# 5_-_Status_Lights.net
KiCad netlist of a schematic drawn in Altium Designer
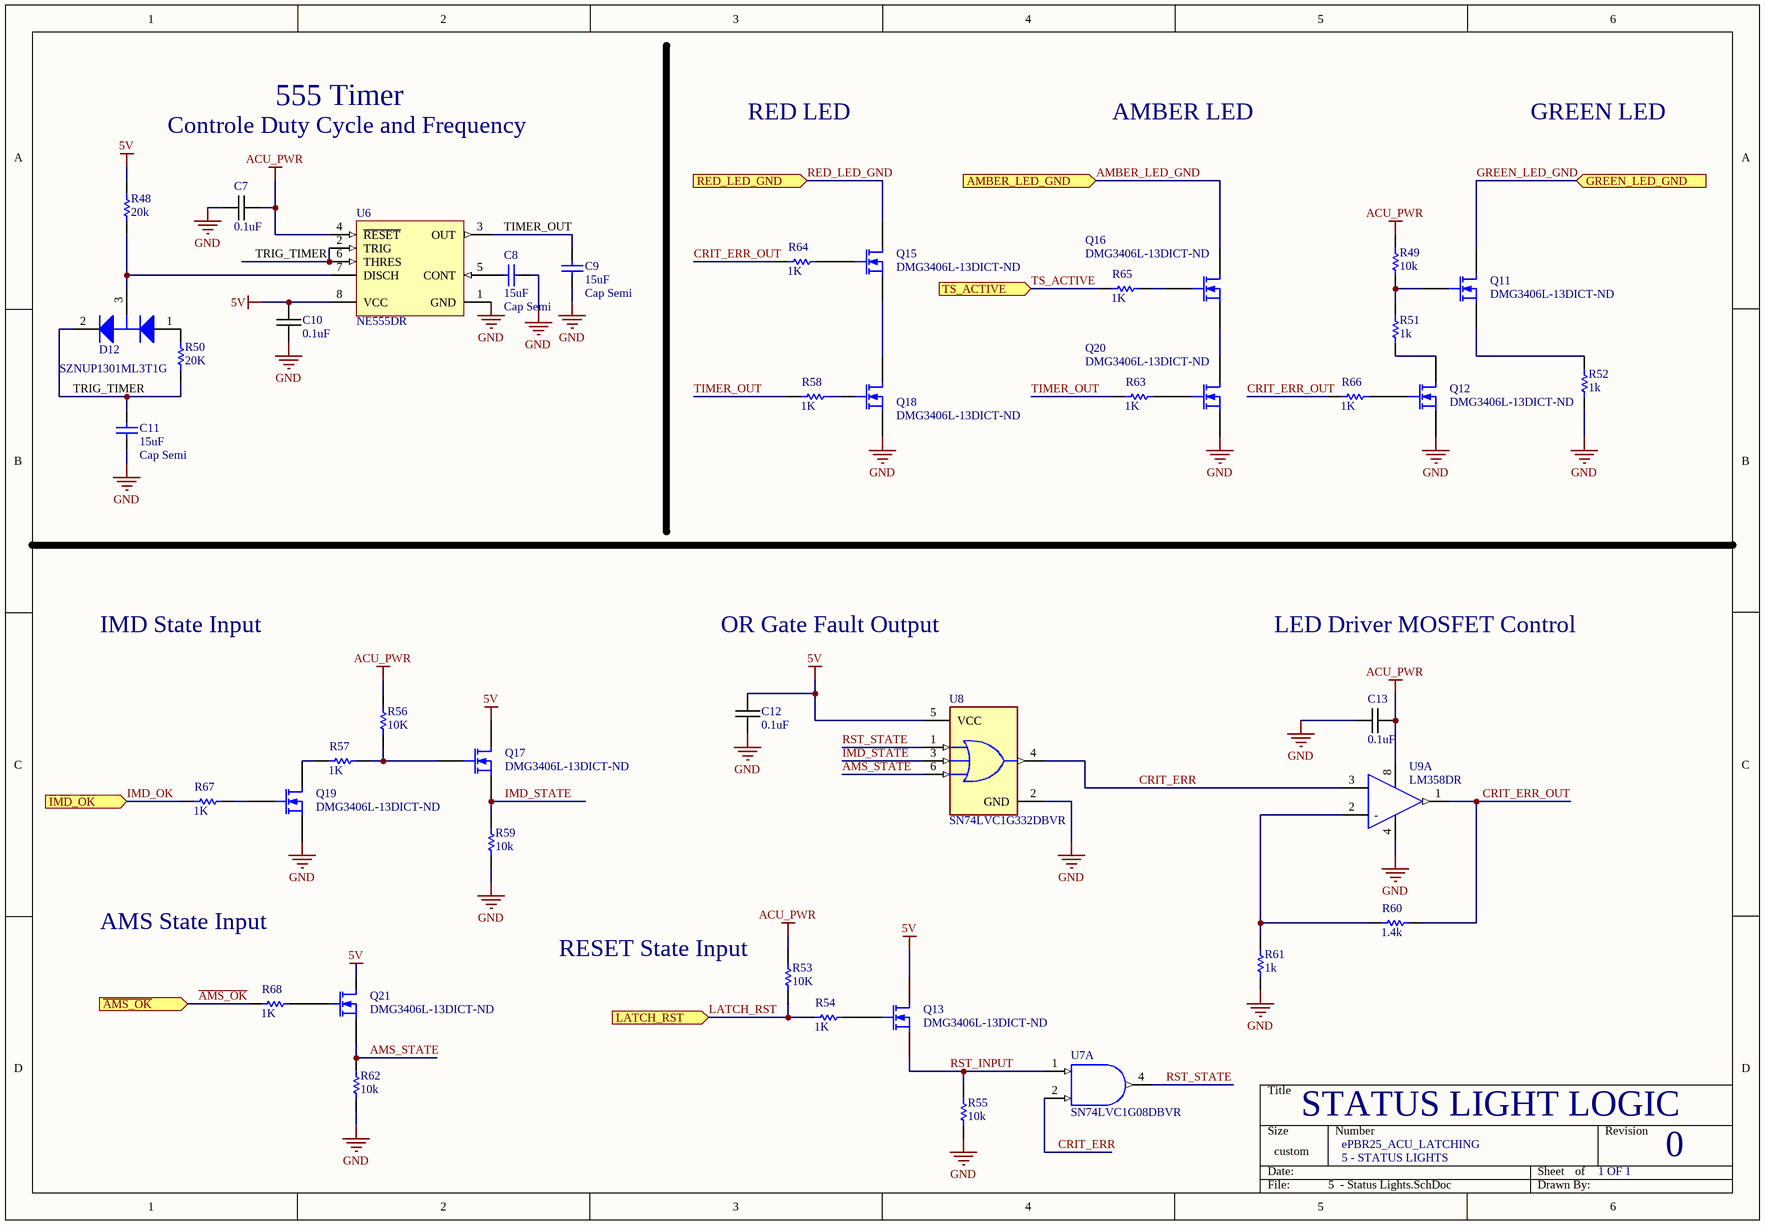
[diagram p0: 5  - Status Lights.SchDoc]

(export (version "E")
  (design (tool "Eeschema 10.0.6"))
  (components
    (comp (ref "C7")
      (value "0.1uF")
      (footprint "1608[0603]")
      (description "CAP CER 0.1UF 50V X7R 0603")
      (fields
        (field (name "MANUFACTURER") "Kemet")
        (field (name "MANUFACTURER PART NUMBER") "C0603C104K5RACAUTO")
      )
      (libsource (lib "vh_altium_library") (part "0805C-100nF-25V-X7R-MUR"))
    )
    (comp (ref "C8")
      (value "Cap Semi")
      (footprint "1608[0603]")
      (description "Capacitor (Semiconductor SIM Model)")
      (fields (field (name "ALTIUM_VALUE") "15uF") (field (name "PUBLISHER") "Altium Limited"))
      (libsource (lib "Miscellaneous Devices") (part "Cap Semi"))
    )
    (comp (ref "C9")
      (value "Cap Semi")
      (footprint "1608[0603]")
      (description "Capacitor (Semiconductor SIM Model)")
      (fields (field (name "ALTIUM_VALUE") "15uF") (field (name "PUBLISHER") "Altium Limited"))
      (libsource (lib "Miscellaneous Devices") (part "Cap Semi"))
    )
    (comp (ref "C10")
      (value "0.1uF")
      (footprint "1608[0603]")
      (description "CAP CER 0.1UF 50V X7R 0603")
      (fields
        (field (name "MANUFACTURER") "Kemet")
        (field (name "MANUFACTURER PART NUMBER") "C0603C104K5RACAUTO")
      )
      (libsource (lib "vh_altium_library") (part "0805C-100nF-25V-X7R-MUR"))
    )
    (comp (ref "C11")
      (value "Cap Semi")
      (footprint "1608[0603]")
      (description "Capacitor (Semiconductor SIM Model)")
      (fields (field (name "ALTIUM_VALUE") "15uF") (field (name "PUBLISHER") "Altium Limited"))
      (libsource (lib "Miscellaneous Devices") (part "Cap Semi"))
    )
    (comp (ref "C12")
      (value "0.1uF")
      (footprint "1608[0603]")
      (description "CAP CER 0.1UF 50V X7R 0603")
      (fields
        (field (name "MANUFACTURER") "Kemet")
        (field (name "MANUFACTURER PART NUMBER") "C0603C104K5RACAUTO")
      )
      (libsource (lib "vh_altium_library") (part "0805C-100nF-25V-X7R-MUR"))
    )
    (comp (ref "C13")
      (value "0.1uF")
      (footprint "1608[0603]")
      (description "CAP CER 0.1UF 50V X7R 0603")
      (fields
        (field (name "MANUFACTURER") "Kemet")
        (field (name "MANUFACTURER PART NUMBER") "C0603C104K5RACAUTO")
      )
      (libsource (lib "vh_altium_library") (part "0805C-100nF-25V-X7R-MUR"))
    )
    (comp (ref "D12")
      (value "SZNUP1301ML3T1G")
      (footprint "ONSC-SOT-23-3-318-08_V")
      (fields (field (name "MANUFACTURER") "On Semiconductor"))
      (libsource (lib "Altium Content Vault") (part "ONSC-NUP1301-SOT-23-3-318-08"))
    )
    (comp (ref "Q11")
      (value "~")
      (footprint "SOT23-GDS")
      (description "N-Channel MOSFET")
      (fields
        (field (name "MANUFACTURER") "Infineon Technologies")
        (field (name "SUPPLIER PART NUMBER 1") "DMG3406L-13DICT-ND")
        (field (name "PUBLISHER") "Altium Limited")
      )
      (libsource (lib "Miscellaneous Devices") (part "MOSFET-N"))
    )
    (comp (ref "Q12")
      (value "~")
      (footprint "SOT23-GDS")
      (description "N-Channel MOSFET")
      (fields
        (field (name "MANUFACTURER") "Infineon Technologies")
        (field (name "SUPPLIER PART NUMBER 1") "DMG3406L-13DICT-ND")
        (field (name "PUBLISHER") "Altium Limited")
      )
      (libsource (lib "Miscellaneous Devices") (part "MOSFET-N"))
    )
    (comp (ref "Q13")
      (value "~")
      (footprint "SOT23-GDS")
      (description "N-Channel MOSFET")
      (fields
        (field (name "MANUFACTURER") "Infineon Technologies")
        (field (name "SUPPLIER PART NUMBER 1") "DMG3406L-13DICT-ND")
        (field (name "PUBLISHER") "Altium Limited")
      )
      (libsource (lib "Miscellaneous Devices") (part "MOSFET-N"))
    )
    (comp (ref "Q15")
      (value "~")
      (footprint "SOT23-GDS")
      (description "N-Channel MOSFET")
      (fields
        (field (name "MANUFACTURER") "Infineon Technologies")
        (field (name "SUPPLIER PART NUMBER 1") "DMG3406L-13DICT-ND")
        (field (name "PUBLISHER") "Altium Limited")
      )
      (libsource (lib "Miscellaneous Devices") (part "MOSFET-N"))
    )
    (comp (ref "Q16")
      (value "~")
      (footprint "SOT23-GDS")
      (description "N-Channel MOSFET")
      (fields
        (field (name "MANUFACTURER") "Infineon Technologies")
        (field (name "SUPPLIER PART NUMBER 1") "DMG3406L-13DICT-ND")
        (field (name "PUBLISHER") "Altium Limited")
      )
      (libsource (lib "Miscellaneous Devices") (part "MOSFET-N"))
    )
    (comp (ref "Q17")
      (value "~")
      (footprint "SOT23-GDS")
      (description "N-Channel MOSFET")
      (fields
        (field (name "MANUFACTURER") "Infineon Technologies")
        (field (name "SUPPLIER PART NUMBER 1") "DMG3406L-13DICT-ND")
        (field (name "PUBLISHER") "Altium Limited")
      )
      (libsource (lib "Miscellaneous Devices") (part "MOSFET-N"))
    )
    (comp (ref "Q18")
      (value "~")
      (footprint "SOT23-GDS")
      (description "N-Channel MOSFET")
      (fields
        (field (name "MANUFACTURER") "Infineon Technologies")
        (field (name "SUPPLIER PART NUMBER 1") "DMG3406L-13DICT-ND")
        (field (name "PUBLISHER") "Altium Limited")
      )
      (libsource (lib "Miscellaneous Devices") (part "MOSFET-N"))
    )
    (comp (ref "Q19")
      (value "~")
      (footprint "SOT23-GDS")
      (description "N-Channel MOSFET")
      (fields
        (field (name "MANUFACTURER") "Infineon Technologies")
        (field (name "SUPPLIER PART NUMBER 1") "DMG3406L-13DICT-ND")
        (field (name "PUBLISHER") "Altium Limited")
      )
      (libsource (lib "Miscellaneous Devices") (part "MOSFET-N"))
    )
    (comp (ref "Q20")
      (value "~")
      (footprint "SOT23-GDS")
      (description "N-Channel MOSFET")
      (fields
        (field (name "MANUFACTURER") "Infineon Technologies")
        (field (name "SUPPLIER PART NUMBER 1") "DMG3406L-13DICT-ND")
        (field (name "PUBLISHER") "Altium Limited")
      )
      (libsource (lib "Miscellaneous Devices") (part "MOSFET-N"))
    )
    (comp (ref "Q21")
      (value "~")
      (footprint "SOT23-GDS")
      (description "N-Channel MOSFET")
      (fields
        (field (name "MANUFACTURER") "Infineon Technologies")
        (field (name "SUPPLIER PART NUMBER 1") "DMG3406L-13DICT-ND")
        (field (name "PUBLISHER") "Altium Limited")
      )
      (libsource (lib "Miscellaneous Devices") (part "MOSFET-N"))
    )
    (comp (ref "R48")
      (value "20k")
      (footprint "RESC0603(1608)_L")
      (description "0603 (1608 Metric) Chip Resistor")
      (libsource (lib "Altium Content Vault") (part "RES_3"))
    )
    (comp (ref "R49")
      (value "10k")
      (footprint "RESC0603(1608)_L")
      (description "0603 (1608 Metric) Chip Resistor")
      (libsource (lib "Altium Content Vault") (part "RES_3"))
    )
    (comp (ref "R50")
      (value "20K")
      (footprint "RESC0603(1608)_L")
      (description "0603 (1608 Metric) Chip Resistor")
      (libsource (lib "Altium Content Vault") (part "RES_3"))
    )
    (comp (ref "R51")
      (value "1k")
      (footprint "RESC0603(1608)_L")
      (description "0603 (1608 Metric) Chip Resistor")
      (libsource (lib "Altium Content Vault") (part "RES_3"))
    )
    (comp (ref "R52")
      (value "1k")
      (footprint "RESC0603(1608)_L")
      (description "0603 (1608 Metric) Chip Resistor")
      (libsource (lib "Altium Content Vault") (part "RES_3"))
    )
    (comp (ref "R53")
      (value "10K")
      (footprint "RESC0603(1608)_L")
      (description "0603 (1608 Metric) Chip Resistor")
      (libsource (lib "Altium Content Vault") (part "RES_3"))
    )
    (comp (ref "R54")
      (value "1K")
      (footprint "RESC0603(1608)_L")
      (description "0603 (1608 Metric) Chip Resistor")
      (libsource (lib "Altium Content Vault") (part "RES_3"))
    )
    (comp (ref "R55")
      (value "10k")
      (footprint "RESC0603(1608)_L")
      (description "0603 (1608 Metric) Chip Resistor")
      (libsource (lib "Altium Content Vault") (part "RES_3"))
    )
    (comp (ref "R56")
      (value "10K")
      (footprint "RESC0603(1608)_L")
      (description "0603 (1608 Metric) Chip Resistor")
      (libsource (lib "Altium Content Vault") (part "RES_3"))
    )
    (comp (ref "R57")
      (value "1K")
      (footprint "RESC0603(1608)_L")
      (description "0603 (1608 Metric) Chip Resistor")
      (libsource (lib "Altium Content Vault") (part "RES_3"))
    )
    (comp (ref "R58")
      (value "1K")
      (footprint "RESC0603(1608)_L")
      (description "0603 (1608 Metric) Chip Resistor")
      (libsource (lib "Altium Content Vault") (part "RES_3"))
    )
    (comp (ref "R59")
      (value "10k")
      (footprint "RESC0603(1608)_L")
      (description "0603 (1608 Metric) Chip Resistor")
      (libsource (lib "Altium Content Vault") (part "RES_3"))
    )
    (comp (ref "R60")
      (value "1.4k")
      (footprint "RESC0603(1608)_L")
      (description "0603 (1608 Metric) Chip Resistor")
      (libsource (lib "Altium Content Vault") (part "RES_3"))
    )
    (comp (ref "R61")
      (value "1k")
      (footprint "RESC0603(1608)_L")
      (description "0603 (1608 Metric) Chip Resistor")
      (libsource (lib "Altium Content Vault") (part "RES_3"))
    )
    (comp (ref "R62")
      (value "10k")
      (footprint "RESC0603(1608)_L")
      (description "0603 (1608 Metric) Chip Resistor")
      (libsource (lib "Altium Content Vault") (part "RES_3"))
    )
    (comp (ref "R63")
      (value "1K")
      (footprint "RESC0603(1608)_L")
      (description "0603 (1608 Metric) Chip Resistor")
      (libsource (lib "Altium Content Vault") (part "RES_3"))
    )
    (comp (ref "R64")
      (value "1K")
      (footprint "RESC0603(1608)_L")
      (description "0603 (1608 Metric) Chip Resistor")
      (libsource (lib "Altium Content Vault") (part "RES_3"))
    )
    (comp (ref "R65")
      (value "1K")
      (footprint "RESC0603(1608)_L")
      (description "0603 (1608 Metric) Chip Resistor")
      (libsource (lib "Altium Content Vault") (part "RES_3"))
    )
    (comp (ref "R66")
      (value "1K")
      (footprint "RESC0603(1608)_L")
      (description "0603 (1608 Metric) Chip Resistor")
      (libsource (lib "Altium Content Vault") (part "RES_3"))
    )
    (comp (ref "R67")
      (value "1K")
      (footprint "RESC0603(1608)_L")
      (description "0603 (1608 Metric) Chip Resistor")
      (libsource (lib "Altium Content Vault") (part "RES_3"))
    )
    (comp (ref "R68")
      (value "1K")
      (footprint "RESC0603(1608)_L")
      (description "0603 (1608 Metric) Chip Resistor")
      (libsource (lib "Altium Content Vault") (part "RES_3"))
    )
    (comp (ref "U6")
      (value "NE555DR")
      (footprint "D0008A_M")
      (libsource (lib "Altium Content Vault") (part "CMP-1685-00007-1"))
    )
    (comp (ref "U7")
      (value "SN74LVC1G08DBVR")
      (footprint "DBV0005A_M")
      (description "Single 2-Input Positive-AND Gate, DBV0005A, LARGE T&R")
      (fields
        (field (name "GENERIC PART NUMBER") "SN74LVC1G08")
        (field (name "MANUFACTURER") "Texas Instruments")
      )
      (libsource (lib "Altium Content Vault") (part "TI-SN74XXX1X08-5"))
    )
    (comp (ref "U8")
      (value "SN74LVC1G332DBVR")
      (footprint "FP-DBV0006A-MFG")
      (description "IC GATE OR 1CH 3-INP SOT23-6")
      (fields
        (field (name "OCTOPART") "https://octopart.com/sn74lvc1g332dbvr-texas+instruments-464996")
        (field (name "MANUFACTURER") "TEXAS INSTRUMENTS")
      )
      (libsource (lib "Altium Content Vault") (part "9bd6587d4ded7f3f3ab4f7d0d680d6b"))
    )
    (comp (ref "U9")
      (value "LM358DR")
      (footprint "FP-D0008A-MFG")
      (description "IC OPAMP GP 2 CIRCUIT 8SOIC")
      (libsource (lib "Altium Content Vault") (part "0afdfe5f461d2cdd85604ff8654be97"))
    )
  )
  (nets
    (net (code "1") (name "/AMBER_LED_GND") (class "Default")
      (node (ref "Q16") (pin "3") (pinfunction "D_3") (pintype "passive"))
    )
    (net (code "2") (name "/AMS_STATE") (class "Default")
      (node (ref "Q21") (pin "2") (pinfunction "S_2") (pintype "passive"))
      (node (ref "R62") (pin "1") (pinfunction "1_1") (pintype "passive"))
      (node (ref "U8") (pin "6") (pinfunction "C_6") (pintype "input"))
    )
    (net (code "3") (name "/CRIT_ERR") (class "Default")
      (node (ref "U7") (pin "2") (pinfunction "B_2") (pintype "input"))
      (node (ref "U8") (pin "4") (pinfunction "Y_4") (pintype "output"))
      (node (ref "U9") (pin "3") (pinfunction "IN1+_3") (pintype "tri_state"))
    )
    (net (code "4") (name "/CRIT_ERR_OUT") (class "Default")
      (node (ref "R60") (pin "2") (pinfunction "2_2") (pintype "passive"))
      (node (ref "R64") (pin "1") (pinfunction "1_1") (pintype "passive"))
      (node (ref "R66") (pin "1") (pinfunction "1_1") (pintype "passive"))
      (node (ref "U9") (pin "1") (pinfunction "1OUT_1") (pintype "output"))
    )
    (net (code "5") (name "/GREEN_LED_GND") (class "Default")
      (node (ref "Q11") (pin "3") (pinfunction "D_3") (pintype "passive"))
    )
    (net (code "6") (name "/IMD_OK") (class "Default")
      (node (ref "R67") (pin "1") (pinfunction "1_1") (pintype "passive"))
    )
    (net (code "7") (name "/IMD_STATE") (class "Default")
      (node (ref "Q17") (pin "2") (pinfunction "S_2") (pintype "passive"))
      (node (ref "R59") (pin "1") (pinfunction "1_1") (pintype "passive"))
      (node (ref "U8") (pin "3") (pinfunction "B_3") (pintype "input"))
    )
    (net (code "8") (name "/LATCH_RST") (class "Default")
      (node (ref "R53") (pin "1") (pinfunction "1_1") (pintype "passive"))
      (node (ref "R54") (pin "1") (pinfunction "1_1") (pintype "passive"))
    )
    (net (code "9") (name "/RED_LED_GND") (class "Default")
      (node (ref "Q15") (pin "3") (pinfunction "D_3") (pintype "passive"))
    )
    (net (code "10") (name "/RST_INPUT") (class "Default")
      (node (ref "Q13") (pin "2") (pinfunction "S_2") (pintype "passive"))
      (node (ref "R55") (pin "1") (pinfunction "1_1") (pintype "passive"))
      (node (ref "U7") (pin "1") (pinfunction "A_1") (pintype "input"))
    )
    (net (code "11") (name "/RST_STATE") (class "Default")
      (node (ref "U7") (pin "4") (pinfunction "Y_4") (pintype "output"))
      (node (ref "U8") (pin "1") (pinfunction "A_1") (pintype "input"))
    )
    (net (code "12") (name "/TIMER_OUT") (class "Default")
      (node (ref "C9") (pin "1") (pinfunction "1_1") (pintype "passive"))
      (node (ref "R58") (pin "1") (pinfunction "1_1") (pintype "passive"))
      (node (ref "R63") (pin "1") (pinfunction "1_1") (pintype "passive"))
      (node (ref "U6") (pin "3") (pinfunction "OUT_3") (pintype "output"))
    )
    (net (code "13") (name "/TRIG_TIMER") (class "Default")
      (node (ref "C11") (pin "1") (pinfunction "1_1") (pintype "passive"))
      (node (ref "D12") (pin "2") (pinfunction "K_2") (pintype "passive"))
      (node (ref "R50") (pin "1") (pinfunction "1_1") (pintype "passive"))
      (node (ref "U6") (pin "2") (pinfunction "TRIG_2") (pintype "input"))
      (node (ref "U6") (pin "6") (pinfunction "THRES_6") (pintype "input"))
    )
    (net (code "14") (name "/TS_ACTIVE") (class "Default")
      (node (ref "R65") (pin "1") (pinfunction "1_1") (pintype "passive"))
    )
    (net (code "15") (name "/~{AMS_OK}") (class "Default")
      (node (ref "R68") (pin "1") (pinfunction "1_1") (pintype "passive"))
    )
    (net (code "16") (name "5V") (class "Default")
      (node (ref "C10") (pin "2") (pintype "passive"))
      (node (ref "C12") (pin "1") (pintype "passive"))
      (node (ref "Q13") (pin "3") (pinfunction "D_3") (pintype "passive"))
      (node (ref "Q17") (pin "3") (pinfunction "D_3") (pintype "passive"))
      (node (ref "Q21") (pin "3") (pinfunction "D_3") (pintype "passive"))
      (node (ref "R48") (pin "1") (pinfunction "1_1") (pintype "passive"))
      (node (ref "U6") (pin "8") (pinfunction "VCC_8") (pintype "power_in"))
      (node (ref "U8") (pin "5") (pinfunction "VCC_5") (pintype "power_in"))
    )
    (net (code "17") (name "ACU_PWR") (class "Default")
      (node (ref "C13") (pin "2") (pintype "passive"))
      (node (ref "C7") (pin "1") (pintype "passive"))
      (node (ref "R49") (pin "1") (pinfunction "1_1") (pintype "passive"))
      (node (ref "R53") (pin "2") (pinfunction "2_2") (pintype "passive"))
      (node (ref "R56") (pin "2") (pinfunction "2_2") (pintype "passive"))
      (node (ref "U6") (pin "4") (pinfunction "~{RESET}_4") (pintype "input"))
      (node (ref "U9") (pin "8") (pinfunction "V+_8") (pintype "power_in"))
    )
    (net (code "18") (name "GND") (class "Default")
      (node (ref "C10") (pin "1") (pintype "passive"))
      (node (ref "C11") (pin "2") (pinfunction "2_2") (pintype "passive"))
      (node (ref "C12") (pin "2") (pintype "passive"))
      (node (ref "C13") (pin "1") (pintype "passive"))
      (node (ref "C7") (pin "2") (pintype "passive"))
      (node (ref "C8") (pin "1") (pinfunction "1_1") (pintype "passive"))
      (node (ref "C9") (pin "2") (pinfunction "2_2") (pintype "passive"))
      (node (ref "Q12") (pin "2") (pinfunction "S_2") (pintype "passive"))
      (node (ref "Q18") (pin "2") (pinfunction "S_2") (pintype "passive"))
      (node (ref "Q19") (pin "2") (pinfunction "S_2") (pintype "passive"))
      (node (ref "Q20") (pin "2") (pinfunction "S_2") (pintype "passive"))
      (node (ref "R52") (pin "1") (pinfunction "1_1") (pintype "passive"))
      (node (ref "R55") (pin "2") (pinfunction "2_2") (pintype "passive"))
      (node (ref "R59") (pin "2") (pinfunction "2_2") (pintype "passive"))
      (node (ref "R61") (pin "2") (pinfunction "2_2") (pintype "passive"))
      (node (ref "R62") (pin "2") (pinfunction "2_2") (pintype "passive"))
      (node (ref "U6") (pin "1") (pinfunction "GND_1") (pintype "power_in"))
      (node (ref "U8") (pin "2") (pinfunction "GND_2") (pintype "power_in"))
      (node (ref "U9") (pin "4") (pinfunction "V-_4") (pintype "power_in"))
    )
    (net (code "19") (name "Net-(D12-A)") (class "Default")
      (node (ref "D12") (pin "1") (pinfunction "A_1") (pintype "passive"))
      (node (ref "R50") (pin "2") (pinfunction "2_2") (pintype "passive"))
    )
    (net (code "20") (name "Net-(D12-K{slash}A)") (class "Default")
      (node (ref "D12") (pin "3") (pinfunction "K/A_3") (pintype "passive"))
      (node (ref "R48") (pin "2") (pinfunction "2_2") (pintype "passive"))
      (node (ref "U6") (pin "7") (pinfunction "DISCH_7") (pintype "open_collector"))
    )
    (net (code "21") (name "Net-(Q11-G)") (class "Default")
      (node (ref "Q11") (pin "1") (pinfunction "G_1") (pintype "passive"))
      (node (ref "R49") (pin "2") (pinfunction "2_2") (pintype "passive"))
      (node (ref "R51") (pin "2") (pinfunction "2_2") (pintype "passive"))
    )
    (net (code "22") (name "Net-(Q11-S)") (class "Default")
      (node (ref "Q11") (pin "2") (pinfunction "S_2") (pintype "passive"))
      (node (ref "R52") (pin "2") (pinfunction "2_2") (pintype "passive"))
    )
    (net (code "23") (name "Net-(Q12-D)") (class "Default")
      (node (ref "Q12") (pin "3") (pinfunction "D_3") (pintype "passive"))
      (node (ref "R51") (pin "1") (pinfunction "1_1") (pintype "passive"))
    )
    (net (code "24") (name "Net-(Q12-G)") (class "Default")
      (node (ref "Q12") (pin "1") (pinfunction "G_1") (pintype "passive"))
      (node (ref "R66") (pin "2") (pinfunction "2_2") (pintype "passive"))
    )
    (net (code "25") (name "Net-(Q13-G)") (class "Default")
      (node (ref "Q13") (pin "1") (pinfunction "G_1") (pintype "passive"))
      (node (ref "R54") (pin "2") (pinfunction "2_2") (pintype "passive"))
    )
    (net (code "26") (name "Net-(Q15-G)") (class "Default")
      (node (ref "Q15") (pin "1") (pinfunction "G_1") (pintype "passive"))
      (node (ref "R64") (pin "2") (pinfunction "2_2") (pintype "passive"))
    )
    (net (code "27") (name "Net-(Q15-S)") (class "Default")
      (node (ref "Q15") (pin "2") (pinfunction "S_2") (pintype "passive"))
      (node (ref "Q18") (pin "3") (pinfunction "D_3") (pintype "passive"))
    )
    (net (code "28") (name "Net-(Q16-G)") (class "Default")
      (node (ref "Q16") (pin "1") (pinfunction "G_1") (pintype "passive"))
      (node (ref "R65") (pin "2") (pinfunction "2_2") (pintype "passive"))
    )
    (net (code "29") (name "Net-(Q16-S)") (class "Default")
      (node (ref "Q16") (pin "2") (pinfunction "S_2") (pintype "passive"))
      (node (ref "Q20") (pin "3") (pinfunction "D_3") (pintype "passive"))
    )
    (net (code "30") (name "Net-(Q17-G)") (class "Default")
      (node (ref "Q17") (pin "1") (pinfunction "G_1") (pintype "passive"))
      (node (ref "R56") (pin "1") (pinfunction "1_1") (pintype "passive"))
      (node (ref "R57") (pin "2") (pinfunction "2_2") (pintype "passive"))
    )
    (net (code "31") (name "Net-(Q18-G)") (class "Default")
      (node (ref "Q18") (pin "1") (pinfunction "G_1") (pintype "passive"))
      (node (ref "R58") (pin "2") (pinfunction "2_2") (pintype "passive"))
    )
    (net (code "32") (name "Net-(Q19-D)") (class "Default")
      (node (ref "Q19") (pin "3") (pinfunction "D_3") (pintype "passive"))
      (node (ref "R57") (pin "1") (pinfunction "1_1") (pintype "passive"))
    )
    (net (code "33") (name "Net-(Q19-G)") (class "Default")
      (node (ref "Q19") (pin "1") (pinfunction "G_1") (pintype "passive"))
      (node (ref "R67") (pin "2") (pinfunction "2_2") (pintype "passive"))
    )
    (net (code "34") (name "Net-(Q20-G)") (class "Default")
      (node (ref "Q20") (pin "1") (pinfunction "G_1") (pintype "passive"))
      (node (ref "R63") (pin "2") (pinfunction "2_2") (pintype "passive"))
    )
    (net (code "35") (name "Net-(Q21-G)") (class "Default")
      (node (ref "Q21") (pin "1") (pinfunction "G_1") (pintype "passive"))
      (node (ref "R68") (pin "2") (pinfunction "2_2") (pintype "passive"))
    )
    (net (code "36") (name "Net-(U6-CONT)") (class "Default")
      (node (ref "C8") (pin "2") (pinfunction "2_2") (pintype "passive"))
      (node (ref "U6") (pin "5") (pinfunction "CONT_5") (pintype "input"))
    )
    (net (code "37") (name "Net-(U9A-IN1-)") (class "Default")
      (node (ref "R60") (pin "1") (pinfunction "1_1") (pintype "passive"))
      (node (ref "R61") (pin "1") (pinfunction "1_1") (pintype "passive"))
      (node (ref "U9") (pin "2") (pinfunction "IN1-_2") (pintype "tri_state"))
    )
  )
)
